# hiiri627v071.net
KiCad netlist of a schematic drawn in Altium Designer
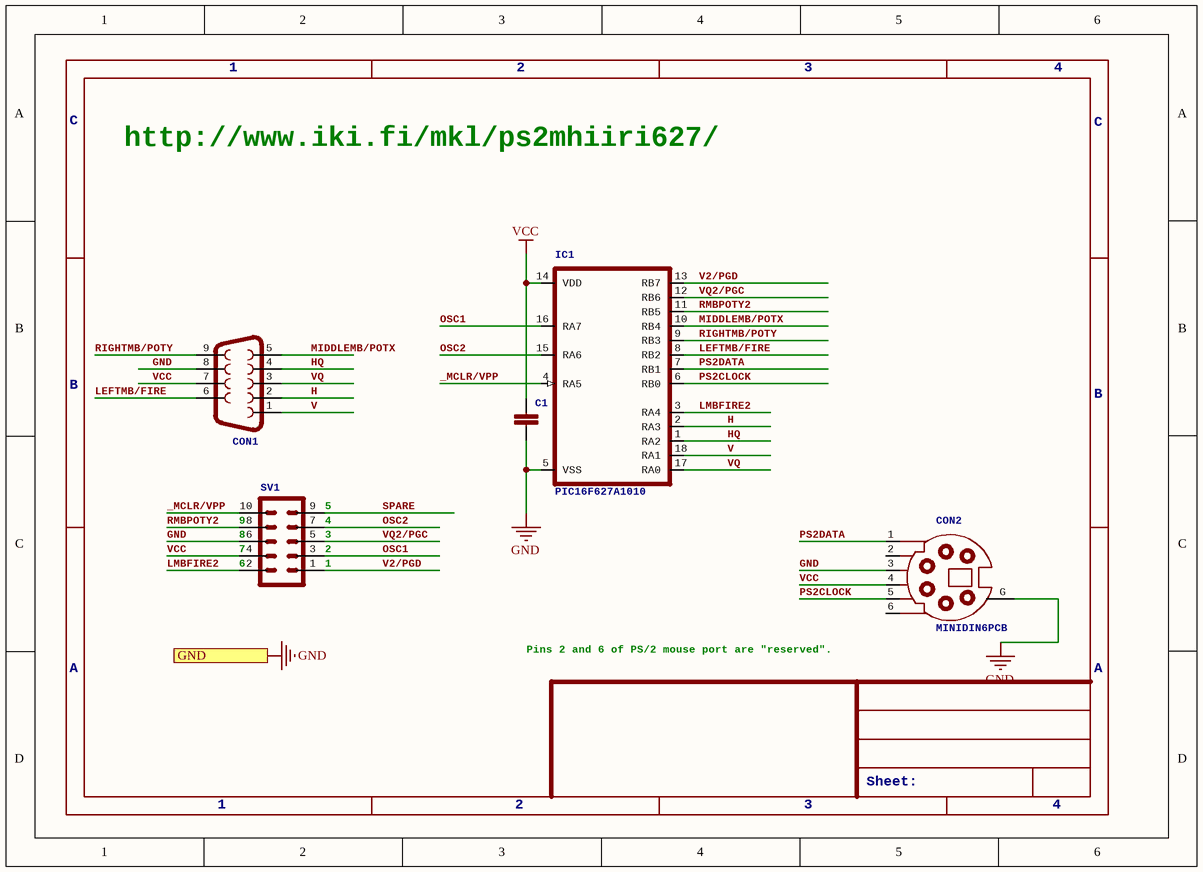
[diagram p0: hiiri627v071.SchDoc]

(export (version "E")
  (design (tool "Eeschema 10.0.6"))
  (components
    (comp (ref "C1")
      (value "C-EUC0805K")
      (footprint "C0805K")
      (description "CAPACITOR, European symbol")
      (libsource (lib "rcl") (part "C-EUC0805K"))
    )
    (comp (ref "CON1")
      (value "F09D")
      (footprint "F09D")
      (description "SUB-D")
      (fields (field (name "LIBRARYNAME") "con-subd"))
      (libsource (lib "con-subd") (part "F09D"))
    )
    (comp (ref "CON2")
      (value "MINIDIN6PCB")
      (footprint "MINIDIN6PCB")
      (fields (field (name "LIBRARYNAME") "0mikacon"))
      (libsource (lib "0mikacon") (part "MINIDIN6PCB"))
    )
    (comp (ref "IC1")
      (value "PIC16F627A1010")
      (footprint "SO18-10101020")
      (fields (field (name "LIBRARYNAME") "0mikalib"))
      (libsource (lib "0mikalib") (part "PIC16F627A1010"))
    )
    (comp (ref "SV1")
      (value "ML10")
      (footprint "ML10")
      (description "HARTING")
      (libsource (lib "con-harting-ml") (part "ML10"))
    )
  )
  (nets
    (net (code "1") (name "/H") (class "Default")
      (node (ref "CON1") (pin "2") (pinfunction "2_2") (pintype "passive"))
      (node (ref "IC1") (pin "2") (pinfunction "RA3_2") (pintype "passive"))
    )
    (net (code "2") (name "/HQ") (class "Default")
      (node (ref "CON1") (pin "4") (pinfunction "4_4") (pintype "passive"))
      (node (ref "IC1") (pin "1") (pinfunction "RA2_1") (pintype "passive"))
    )
    (net (code "3") (name "/LEFTMB{slash}FIRE") (class "Default")
      (node (ref "CON1") (pin "6") (pinfunction "6_6") (pintype "passive"))
      (node (ref "IC1") (pin "8") (pinfunction "RB2_8") (pintype "passive"))
    )
    (net (code "4") (name "/LMBFIRE2") (class "Default")
      (node (ref "IC1") (pin "3") (pinfunction "RA4_3") (pintype "passive"))
      (node (ref "SV1") (pin "2") (pinfunction "2_2") (pintype "passive"))
    )
    (net (code "5") (name "/MIDDLEMB{slash}POTX") (class "Default")
      (node (ref "CON1") (pin "5") (pinfunction "5_5") (pintype "passive"))
      (node (ref "IC1") (pin "10") (pinfunction "RB4_10") (pintype "passive"))
    )
    (net (code "6") (name "/OSC1") (class "Default")
      (node (ref "IC1") (pin "16") (pinfunction "RA7_16") (pintype "passive"))
      (node (ref "SV1") (pin "3") (pinfunction "3_3") (pintype "passive"))
    )
    (net (code "7") (name "/OSC2") (class "Default")
      (node (ref "IC1") (pin "15") (pinfunction "RA6_15") (pintype "passive"))
      (node (ref "SV1") (pin "7") (pinfunction "7_7") (pintype "passive"))
    )
    (net (code "8") (name "/PS2CLOCK") (class "Default")
      (node (ref "CON2") (pin "5") (pinfunction "5_5") (pintype "passive"))
      (node (ref "IC1") (pin "6") (pinfunction "RB0_6") (pintype "passive"))
    )
    (net (code "9") (name "/PS2DATA") (class "Default")
      (node (ref "CON2") (pin "1") (pinfunction "1_1") (pintype "passive"))
      (node (ref "IC1") (pin "7") (pinfunction "RB1_7") (pintype "passive"))
    )
    (net (code "10") (name "/RIGHTMB{slash}POTY") (class "Default")
      (node (ref "CON1") (pin "9") (pinfunction "9_9") (pintype "passive"))
      (node (ref "IC1") (pin "9") (pinfunction "RB3_9") (pintype "passive"))
    )
    (net (code "11") (name "/RMBPOTY2") (class "Default")
      (node (ref "IC1") (pin "11") (pinfunction "RB5_11") (pintype "passive"))
      (node (ref "SV1") (pin "8") (pinfunction "8_8") (pintype "passive"))
    )
    (net (code "12") (name "/SPARE") (class "Default")
      (node (ref "SV1") (pin "9") (pinfunction "9_9") (pintype "passive"))
    )
    (net (code "13") (name "/V") (class "Default")
      (node (ref "CON1") (pin "1") (pinfunction "1_1") (pintype "passive"))
      (node (ref "IC1") (pin "18") (pinfunction "RA1_18") (pintype "passive"))
    )
    (net (code "14") (name "/V2{slash}PGD") (class "Default")
      (node (ref "IC1") (pin "13") (pinfunction "RB7_13") (pintype "passive"))
      (node (ref "SV1") (pin "1") (pinfunction "1_1") (pintype "passive"))
    )
    (net (code "15") (name "/VQ") (class "Default")
      (node (ref "CON1") (pin "3") (pinfunction "3_3") (pintype "passive"))
      (node (ref "IC1") (pin "17") (pinfunction "RA0_17") (pintype "passive"))
    )
    (net (code "16") (name "/VQ2{slash}PGC") (class "Default")
      (node (ref "IC1") (pin "12") (pinfunction "RB6_12") (pintype "passive"))
      (node (ref "SV1") (pin "5") (pinfunction "5_5") (pintype "passive"))
    )
    (net (code "17") (name "/_MCLR{slash}VPP") (class "Default")
      (node (ref "IC1") (pin "4") (pinfunction "RA5_4") (pintype "input"))
      (node (ref "SV1") (pin "10") (pinfunction "10_10") (pintype "passive"))
    )
    (net (code "18") (name "GND") (class "Default")
      (node (ref "C1") (pin "2") (pinfunction "2_2") (pintype "passive"))
      (node (ref "CON1") (pin "8") (pinfunction "8_8") (pintype "passive"))
      (node (ref "CON2") (pin "3") (pinfunction "3_3") (pintype "passive"))
      (node (ref "CON2") (pin "G") (pinfunction "G_G") (pintype "passive"))
      (node (ref "IC1") (pin "5") (pinfunction "VSS_5") (pintype "power_in"))
      (node (ref "SV1") (pin "6") (pinfunction "6_6") (pintype "passive"))
    )
    (net (code "19") (name "VCC") (class "Default")
      (node (ref "C1") (pin "1") (pinfunction "1_1") (pintype "passive"))
      (node (ref "CON1") (pin "7") (pinfunction "7_7") (pintype "passive"))
      (node (ref "CON2") (pin "4") (pinfunction "4_4") (pintype "passive"))
      (node (ref "IC1") (pin "14") (pinfunction "VDD_14") (pintype "power_in"))
      (node (ref "SV1") (pin "4") (pinfunction "4_4") (pintype "passive"))
    )
    (net (code "20") (name "unconnected-(CON2-Pad2)") (class "Default")
      (node (ref "CON2") (pin "2") (pinfunction "2_2") (pintype "passive"))
    )
    (net (code "21") (name "unconnected-(CON2-Pad6)") (class "Default")
      (node (ref "CON2") (pin "6") (pinfunction "6_6") (pintype "passive"))
    )
  )
)
